# skematik_rangkaian_node.net
KiCad netlist of a schematic drawn in EAGLE
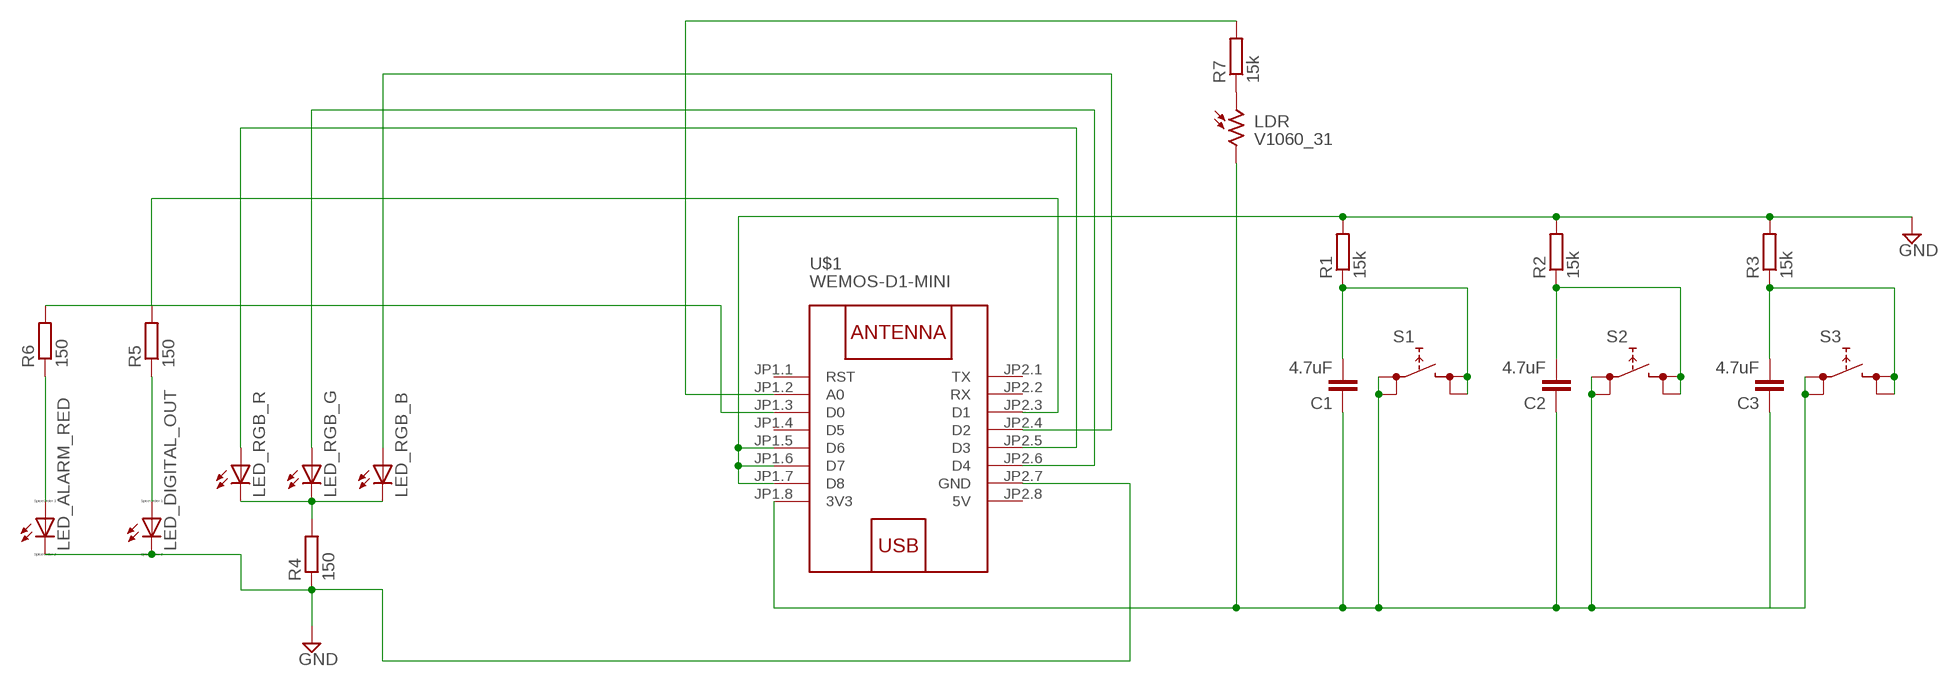
[diagram p0: schematic, sheet 1]

(export (version "E")
  (design (tool "Eeschema 10.0.6"))
  (components
    (comp (ref "C1")
      (value "4.7uF")
      (footprint "eagle-import:C5B5.5")
      (libsource (lib "eagle-import") (part "C5/5.5"))
    )
    (comp (ref "C2")
      (value "4.7uF")
      (footprint "eagle-import:C5B5.5")
      (libsource (lib "eagle-import") (part "C5/5.5"))
    )
    (comp (ref "C3")
      (value "4.7uF")
      (footprint "eagle-import:C5B5.5")
      (libsource (lib "eagle-import") (part "C5/5.5"))
    )
    (comp (ref "LDR")
      (value "V1060_31")
      (footprint "eagle-import:TO-5_V10")
      (libsource (lib "eagle-import") (part "?1060V_31"))
    )
    (comp (ref "LED_ALARM_RED")
      (value "LED_E")
      (footprint "eagle-import:LED_1206")
      (libsource (lib "eagle-import") (part "LED_E"))
    )
    (comp (ref "LED_DIGITAL_OUT")
      (value "LED_E")
      (footprint "eagle-import:LED_1206")
      (libsource (lib "eagle-import") (part "LED_E"))
    )
    (comp (ref "LED_RGB_")
      (value "GM5WA94310A")
      (footprint "eagle-import:GM5WA94310A")
      (libsource (lib "eagle-import") (part "GM5WA94310A"))
    )
    (comp (ref "R1")
      (value "15k")
      (footprint "eagle-import:0204V")
      (libsource (lib "eagle-import") (part "R-EU_0204/2V"))
    )
    (comp (ref "R2")
      (value "15k")
      (footprint "eagle-import:0204V")
      (libsource (lib "eagle-import") (part "R-EU_0204/2V"))
    )
    (comp (ref "R3")
      (value "15k")
      (footprint "eagle-import:0204V")
      (libsource (lib "eagle-import") (part "R-EU_0204/2V"))
    )
    (comp (ref "R4")
      (value "150")
      (footprint "eagle-import:0204V")
      (libsource (lib "eagle-import") (part "R-EU_0204/2V"))
    )
    (comp (ref "R5")
      (value "150")
      (footprint "eagle-import:0204V")
      (libsource (lib "eagle-import") (part "R-EU_0204/2V"))
    )
    (comp (ref "R6")
      (value "150")
      (footprint "eagle-import:0204V")
      (libsource (lib "eagle-import") (part "R-EU_0204/2V"))
    )
    (comp (ref "R7")
      (value "15k")
      (footprint "eagle-import:0204V")
      (libsource (lib "eagle-import") (part "R-EU_0204/2V"))
    )
    (comp (ref "S1")
      (value "REKN")
      (footprint "eagle-import:REKN")
      (libsource (lib "eagle-import") (part "REKN"))
    )
    (comp (ref "S2")
      (value "REKN")
      (footprint "eagle-import:REKN")
      (libsource (lib "eagle-import") (part "REKN"))
    )
    (comp (ref "S3")
      (value "REKN")
      (footprint "eagle-import:REKN")
      (libsource (lib "eagle-import") (part "REKN"))
    )
    (comp (ref "U$1")
      (value "WEMOS-D1-MINI")
      (footprint "eagle-import:WEMOS-D1-MINI")
      (libsource (lib "eagle-import") (part "WEMOS-D1-MINI"))
    )
  )
  (nets
    (net (code "1") (name "/5V") (class "Default")
      (node (ref "U$1") (pin "JP2.8") (pinfunction "5V_JP2.8") (pintype "power_in"))
    )
    (net (code "2") (name "GND") (class "Default")
      (node (ref "LED_ALARM_RED") (pin "C") (pinfunction "C_C") (pintype "passive"))
      (node (ref "LED_DIGITAL_OUT") (pin "C") (pinfunction "C_C") (pintype "passive"))
      (node (ref "R1") (pin "2") (pinfunction "2_2") (pintype "passive"))
      (node (ref "R2") (pin "2") (pinfunction "2_2") (pintype "passive"))
      (node (ref "R3") (pin "2") (pinfunction "2_2") (pintype "passive"))
      (node (ref "R4") (pin "1") (pinfunction "1_1") (pintype "passive"))
      (node (ref "U$1") (pin "JP1.5") (pinfunction "D6_JP1.5") (pintype "bidirectional"))
      (node (ref "U$1") (pin "JP1.6") (pinfunction "D7_JP1.6") (pintype "bidirectional"))
      (node (ref "U$1") (pin "JP1.7") (pinfunction "D8_JP1.7") (pintype "bidirectional"))
      (node (ref "U$1") (pin "JP2.7") (pinfunction "GND_JP2.7") (pintype "power_in"))
    )
    (net (code "3") (name "Net-(C1-Pad2)") (class "Default")
      (node (ref "C1") (pin "2") (pinfunction "2_2") (pintype "passive"))
      (node (ref "R1") (pin "1") (pinfunction "1_1") (pintype "passive"))
      (node (ref "S1") (pin "1A") (pinfunction "1_1A") (pintype "passive"))
      (node (ref "S1") (pin "1B") (pinfunction "1_1B") (pintype "passive"))
    )
    (net (code "4") (name "Net-(C2-Pad2)") (class "Default")
      (node (ref "C2") (pin "2") (pinfunction "2_2") (pintype "passive"))
      (node (ref "R2") (pin "1") (pinfunction "1_1") (pintype "passive"))
      (node (ref "S2") (pin "1A") (pinfunction "1_1A") (pintype "passive"))
      (node (ref "S2") (pin "1B") (pinfunction "1_1B") (pintype "passive"))
    )
    (net (code "5") (name "Net-(C3-Pad2)") (class "Default")
      (node (ref "C3") (pin "2") (pinfunction "2_2") (pintype "passive"))
      (node (ref "R3") (pin "1") (pinfunction "1_1") (pintype "passive"))
      (node (ref "S3") (pin "1A") (pinfunction "1_1A") (pintype "passive"))
      (node (ref "S3") (pin "1B") (pinfunction "1_1B") (pintype "passive"))
    )
    (net (code "6") (name "Net-(LDR-Pad1)") (class "Default")
      (node (ref "LDR") (pin "1") (pinfunction "1_1") (pintype "passive"))
      (node (ref "R7") (pin "1") (pinfunction "1_1") (pintype "passive"))
    )
    (net (code "7") (name "Net-(LED_ALARM_RED-PadA)") (class "Default")
      (node (ref "LED_ALARM_RED") (pin "A") (pinfunction "A_A") (pintype "passive"))
      (node (ref "R6") (pin "1") (pinfunction "1_1") (pintype "passive"))
    )
    (net (code "8") (name "Net-(LED_DIGITAL_OUT-PadA)") (class "Default")
      (node (ref "LED_DIGITAL_OUT") (pin "A") (pinfunction "A_A") (pintype "passive"))
      (node (ref "R5") (pin "1") (pinfunction "1_1") (pintype "passive"))
    )
    (net (code "9") (name "Net-(LED_RGB_A-A)") (class "Default")
      (node (ref "LED_RGB_") (pin "1") (pinfunction "A_1") (pintype "passive"))
      (node (ref "U$1") (pin "JP2.4") (pinfunction "D2_JP2.4") (pintype "bidirectional"))
    )
    (net (code "10") (name "Net-(LED_RGB_A-C)") (class "Default")
      (node (ref "LED_RGB_") (pin "4") (pinfunction "C_4") (pintype "passive"))
      (node (ref "LED_RGB_") (pin "5") (pinfunction "C_5") (pintype "passive"))
      (node (ref "LED_RGB_") (pin "6") (pinfunction "C_6") (pintype "passive"))
      (node (ref "R4") (pin "2") (pinfunction "2_2") (pintype "passive"))
    )
    (net (code "11") (name "Net-(LED_RGB_B-A)") (class "Default")
      (node (ref "LED_RGB_") (pin "3") (pinfunction "A_3") (pintype "passive"))
      (node (ref "U$1") (pin "JP2.6") (pinfunction "D4_JP2.6") (pintype "bidirectional"))
    )
    (net (code "12") (name "Net-(LED_RGB_C-A)") (class "Default")
      (node (ref "LED_RGB_") (pin "2") (pinfunction "A_2") (pintype "passive"))
      (node (ref "U$1") (pin "JP2.5") (pinfunction "D3_JP2.5") (pintype "bidirectional"))
    )
    (net (code "13") (name "Net-(U$1-3V3)") (class "Default")
      (node (ref "C1") (pin "1") (pinfunction "1_1") (pintype "passive"))
      (node (ref "C2") (pin "1") (pinfunction "1_1") (pintype "passive"))
      (node (ref "C3") (pin "1") (pinfunction "1_1") (pintype "passive"))
      (node (ref "LDR") (pin "2") (pinfunction "2_2") (pintype "passive"))
      (node (ref "S1") (pin "0A") (pinfunction "0_0A") (pintype "passive"))
      (node (ref "S1") (pin "0B") (pinfunction "0_0B") (pintype "passive"))
      (node (ref "S2") (pin "0A") (pinfunction "0_0A") (pintype "passive"))
      (node (ref "S2") (pin "0B") (pinfunction "0_0B") (pintype "passive"))
      (node (ref "S3") (pin "0A") (pinfunction "0_0A") (pintype "passive"))
      (node (ref "S3") (pin "0B") (pinfunction "0_0B") (pintype "passive"))
      (node (ref "U$1") (pin "JP1.8") (pinfunction "3V3_JP1.8") (pintype "power_in"))
    )
    (net (code "14") (name "Net-(U$1-A0)") (class "Default")
      (node (ref "R7") (pin "2") (pinfunction "2_2") (pintype "passive"))
      (node (ref "U$1") (pin "JP1.2") (pinfunction "A0_JP1.2") (pintype "bidirectional"))
    )
    (net (code "15") (name "Net-(U$1-D0)") (class "Default")
      (node (ref "R6") (pin "2") (pinfunction "2_2") (pintype "passive"))
      (node (ref "U$1") (pin "JP1.3") (pinfunction "D0_JP1.3") (pintype "bidirectional"))
    )
    (net (code "16") (name "Net-(U$1-D1)") (class "Default")
      (node (ref "R5") (pin "2") (pinfunction "2_2") (pintype "passive"))
      (node (ref "U$1") (pin "JP2.3") (pinfunction "D1_JP2.3") (pintype "bidirectional"))
    )
    (net (code "17") (name "unconnected-(U$1-D5-PadJP1.4)") (class "Default")
      (node (ref "U$1") (pin "JP1.4") (pinfunction "D5_JP1.4") (pintype "bidirectional"))
    )
    (net (code "18") (name "unconnected-(U$1-RST-PadJP1.1)") (class "Default")
      (node (ref "U$1") (pin "JP1.1") (pinfunction "RST_JP1.1") (pintype "bidirectional"))
    )
    (net (code "19") (name "unconnected-(U$1-RX-PadJP2.2)") (class "Default")
      (node (ref "U$1") (pin "JP2.2") (pinfunction "RX_JP2.2") (pintype "bidirectional"))
    )
    (net (code "20") (name "unconnected-(U$1-TX-PadJP2.1)") (class "Default")
      (node (ref "U$1") (pin "JP2.1") (pinfunction "TX_JP2.1") (pintype "bidirectional"))
    )
  )
)
